# Movuino_Dongle_v0_94.net
KiCad netlist of a schematic drawn in EAGLE
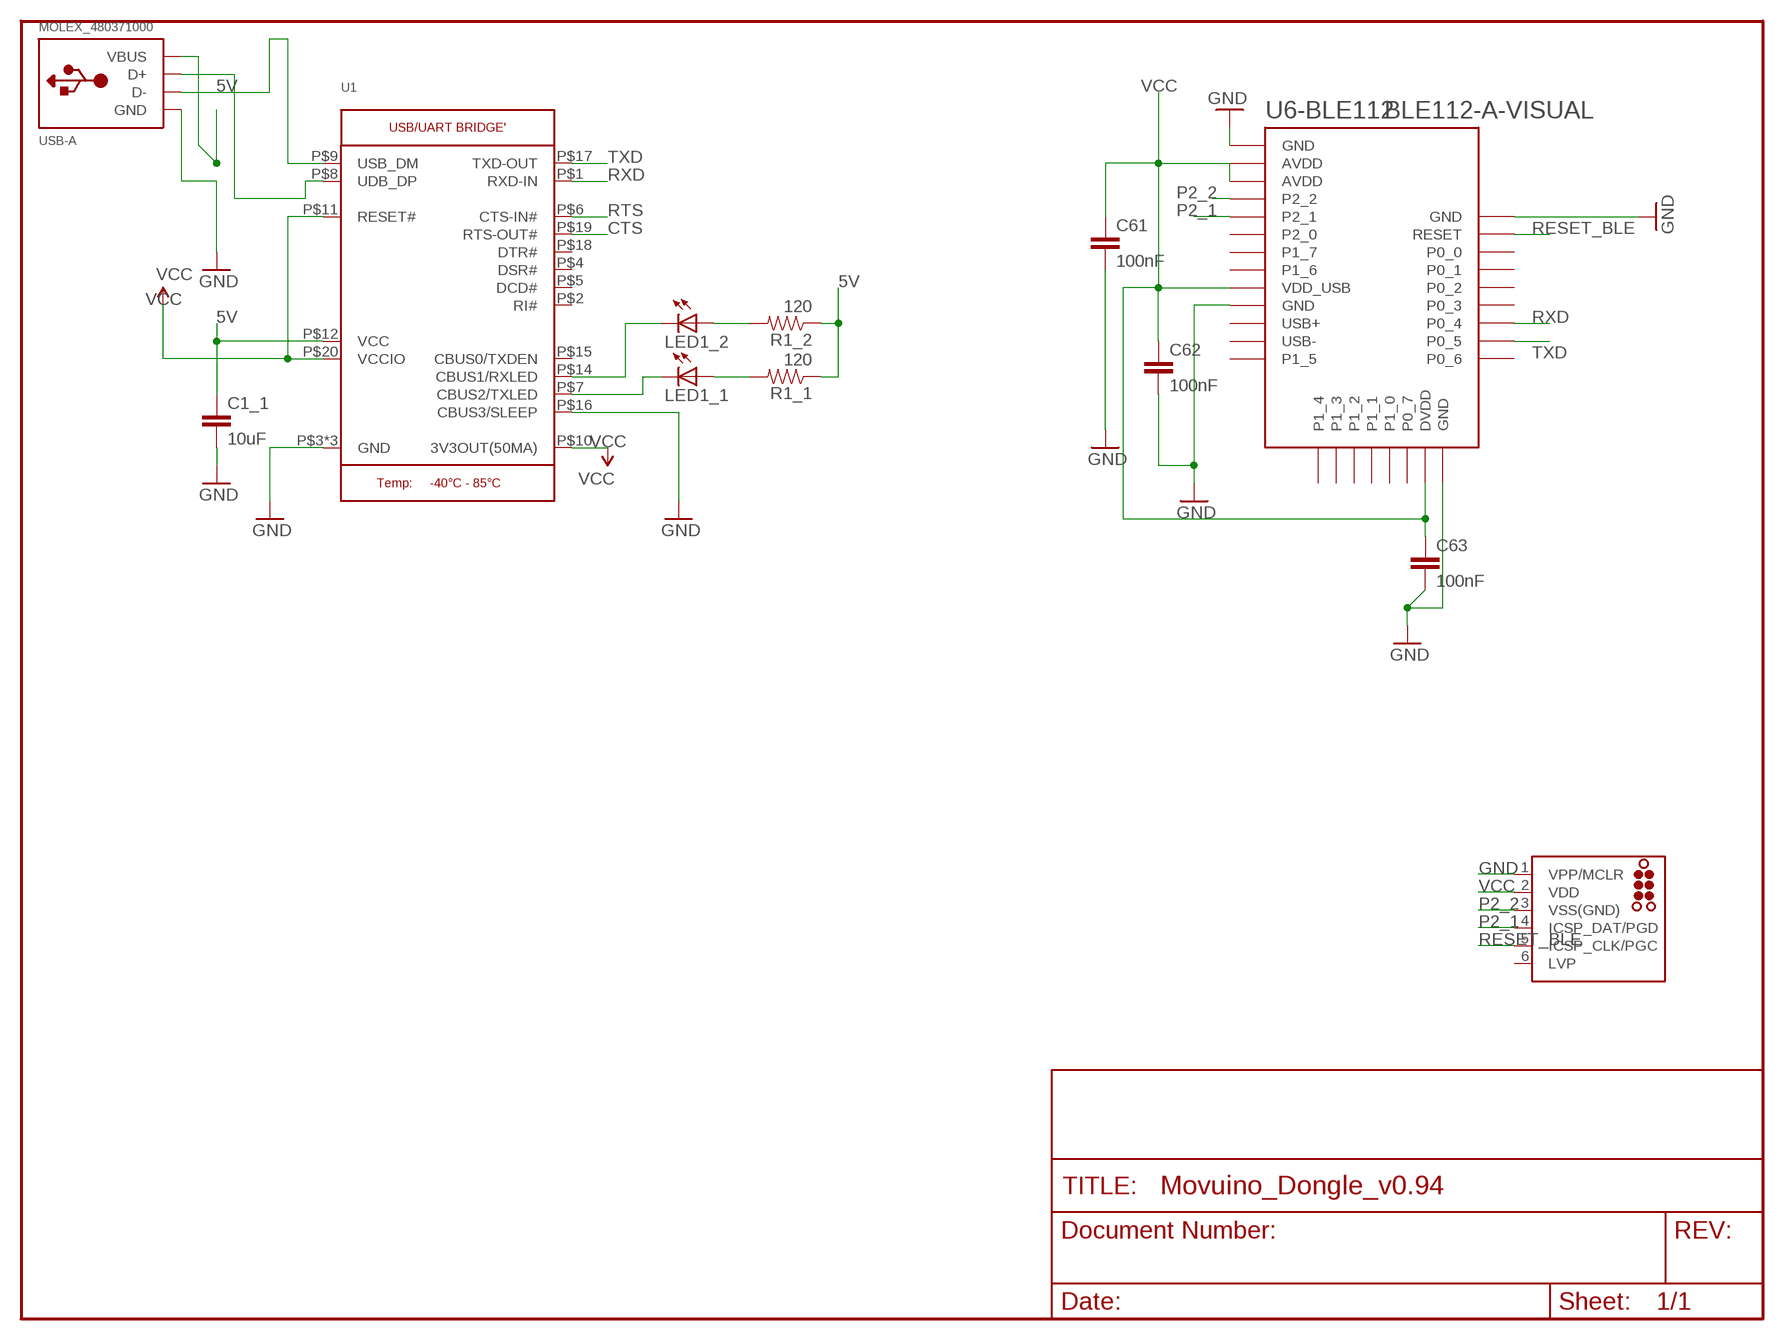
[diagram p0: schematic, sheet 1]

(export (version "E")
  (design (tool "Eeschema 10.0.6"))
  (components
    (comp (ref "C1_1")
      (value "10uF")
      (footprint "eagle-import:0402-CAP")
      (libsource (lib "eagle-import") (part "CAP0402-CAP"))
    )
    (comp (ref "C61")
      (value "100nF")
      (footprint "eagle-import:0402-CAP")
      (libsource (lib "eagle-import") (part "CAP0402-CAP"))
    )
    (comp (ref "C62")
      (value "100nF")
      (footprint "eagle-import:0402-CAP")
      (libsource (lib "eagle-import") (part "CAP0402-CAP"))
    )
    (comp (ref "C63")
      (value "100nF")
      (footprint "eagle-import:0402-CAP")
      (libsource (lib "eagle-import") (part "CAP0402-CAP"))
    )
    (comp (ref "J1")
      (value "TC2030-MCP-NL")
      (footprint "eagle-import:TC2030-MCP-NL")
      (libsource (lib "eagle-import") (part "TC2030-MCP-NL"))
    )
    (comp (ref "LED1_1")
      (value "LED0603")
      (footprint "eagle-import:LED-0603")
      (libsource (lib "eagle-import") (part "LED0603"))
    )
    (comp (ref "LED1_2")
      (value "LED0603")
      (footprint "eagle-import:LED-0603")
      (libsource (lib "eagle-import") (part "LED0603"))
    )
    (comp (ref "MOLEX_480371000")
      (value "USB-A")
      (footprint "eagle-import:MOLEX_480371000")
      (libsource (lib "eagle-import") (part "USB-A"))
    )
    (comp (ref "R1_1")
      (value "120")
      (footprint "eagle-import:0402-RES")
      (libsource (lib "eagle-import") (part "RESISTOR0402-RES"))
    )
    (comp (ref "R1_2")
      (value "120")
      (footprint "eagle-import:0402-RES")
      (libsource (lib "eagle-import") (part "RESISTOR0402-RES"))
    )
    (comp (ref "U1")
      (value "MICROBUILDER_FT231X")
      (footprint "eagle-import:MICROBUILDER_QFN20_4MM")
      (libsource (lib "eagle-import") (part "MICROBUILDER_FT231X"))
    )
    (comp (ref "U6-BLE112")
      (value "BLE112-A-VISUAL")
      (footprint "eagle-import:BLE112-A")
      (libsource (lib "eagle-import") (part "BLE112-A-VISUAL"))
    )
  )
  (nets
    (net (code "1") (name "/5V") (class "Default")
      (node (ref "C1_1") (pin "1") (pinfunction "1_1") (pintype "passive"))
      (node (ref "MOLEX_480371000") (pin "1") (pinfunction "VBUS_1") (pintype "power_in"))
      (node (ref "R1_1") (pin "1") (pinfunction "1_1") (pintype "passive"))
      (node (ref "R1_2") (pin "1") (pinfunction "1_1") (pintype "passive"))
      (node (ref "U1") (pin "P$12") (pinfunction "VCC_P$12") (pintype "power_in"))
    )
    (net (code "2") (name "/CTS") (class "Default")
      (node (ref "U1") (pin "P$19") (pinfunction "RTS-OUT#_P$19") (pintype "output"))
    )
    (net (code "3") (name "/P2_1") (class "Default")
      (node (ref "J1") (pin "4") (pinfunction "ICSP_DAT/PGD_4") (pintype "bidirectional"))
      (node (ref "U6-BLE112") (pin "P2_1") (pinfunction "P2_1_P2_1") (pintype "bidirectional"))
    )
    (net (code "4") (name "/P2_2") (class "Default")
      (node (ref "J1") (pin "3") (pinfunction "VSS(GND)_3") (pintype "power_in"))
      (node (ref "U6-BLE112") (pin "P2_2") (pinfunction "P2_2_P2_2") (pintype "bidirectional"))
    )
    (net (code "5") (name "/RESET_BLE") (class "Default")
      (node (ref "J1") (pin "5") (pinfunction "ICSP_CLK/PGC_5") (pintype "output"))
      (node (ref "U6-BLE112") (pin "RESET") (pinfunction "RESET_RESET") (pintype "input"))
    )
    (net (code "6") (name "/RTS") (class "Default")
      (node (ref "U1") (pin "P$6") (pinfunction "CTS-IN#_P$6") (pintype "input"))
    )
    (net (code "7") (name "/RXD") (class "Default")
      (node (ref "U1") (pin "P$1") (pinfunction "RXD-IN_P$1") (pintype "input"))
      (node (ref "U6-BLE112") (pin "P0_4") (pinfunction "P0_4_P0_4") (pintype "bidirectional"))
    )
    (net (code "8") (name "/TXD") (class "Default")
      (node (ref "U1") (pin "P$17") (pinfunction "TXD-OUT_P$17") (pintype "output"))
      (node (ref "U6-BLE112") (pin "P0_5") (pinfunction "P0_5_P0_5") (pintype "bidirectional"))
    )
    (net (code "9") (name "GND") (class "Default")
      (node (ref "C1_1") (pin "2") (pinfunction "2_2") (pintype "passive"))
      (node (ref "C61") (pin "2") (pinfunction "2_2") (pintype "passive"))
      (node (ref "C62") (pin "2") (pinfunction "2_2") (pintype "passive"))
      (node (ref "C63") (pin "2") (pinfunction "2_2") (pintype "passive"))
      (node (ref "J1") (pin "1") (pinfunction "VPP/MCLR_1") (pintype "passive"))
      (node (ref "MOLEX_480371000") (pin "4") (pinfunction "GND_4") (pintype "power_in"))
      (node (ref "U1") (pin "P$13") (pinfunction "GND_P$13") (pintype "power_in"))
      (node (ref "U1") (pin "P$16") (pinfunction "CBUS3/SLEEP_P$16") (pintype "bidirectional"))
      (node (ref "U1") (pin "P$21") (pinfunction "GND_P$21") (pintype "power_in"))
      (node (ref "U1") (pin "P$3") (pinfunction "GND_P$3") (pintype "power_in"))
      (node (ref "U6-BLE112") (pin "GND1") (pinfunction "GND_GND1") (pintype "power_in"))
      (node (ref "U6-BLE112") (pin "GND2") (pinfunction "GND_GND2") (pintype "power_in"))
      (node (ref "U6-BLE112") (pin "GND3") (pinfunction "GND_GND3") (pintype "power_in"))
      (node (ref "U6-BLE112") (pin "GND4") (pinfunction "GND_GND4") (pintype "power_in"))
    )
    (net (code "10") (name "Net-(LED1_1-PadA)") (class "Default")
      (node (ref "LED1_1") (pin "A") (pinfunction "A_A") (pintype "passive"))
      (node (ref "R1_1") (pin "2") (pinfunction "2_2") (pintype "passive"))
    )
    (net (code "11") (name "Net-(LED1_2-PadA)") (class "Default")
      (node (ref "LED1_2") (pin "A") (pinfunction "A_A") (pintype "passive"))
      (node (ref "R1_2") (pin "2") (pinfunction "2_2") (pintype "passive"))
    )
    (net (code "12") (name "Net-(MOLEX_480371000-D+)") (class "Default")
      (node (ref "MOLEX_480371000") (pin "3") (pinfunction "D+_3") (pintype "bidirectional"))
      (node (ref "U1") (pin "P$8") (pinfunction "UDB_DP_P$8") (pintype "input"))
    )
    (net (code "13") (name "Net-(MOLEX_480371000-D-)") (class "Default")
      (node (ref "MOLEX_480371000") (pin "2") (pinfunction "D-_2") (pintype "bidirectional"))
      (node (ref "U1") (pin "P$9") (pinfunction "USB_DM_P$9") (pintype "input"))
    )
    (net (code "14") (name "Net-(U1-CBUS1{slash}RXLED)") (class "Default")
      (node (ref "LED1_2") (pin "C") (pinfunction "C_C") (pintype "passive"))
      (node (ref "U1") (pin "P$14") (pinfunction "CBUS1/RXLED_P$14") (pintype "bidirectional"))
    )
    (net (code "15") (name "Net-(U1-CBUS2{slash}TXLED)") (class "Default")
      (node (ref "LED1_1") (pin "C") (pinfunction "C_C") (pintype "passive"))
      (node (ref "U1") (pin "P$7") (pinfunction "CBUS2/TXLED_P$7") (pintype "bidirectional"))
    )
    (net (code "16") (name "VCC") (class "Default")
      (node (ref "C61") (pin "1") (pinfunction "1_1") (pintype "passive"))
      (node (ref "C62") (pin "1") (pinfunction "1_1") (pintype "passive"))
      (node (ref "C63") (pin "1") (pinfunction "1_1") (pintype "passive"))
      (node (ref "J1") (pin "2") (pinfunction "VDD_2") (pintype "power_in"))
      (node (ref "U1") (pin "P$10") (pinfunction "3V3OUT(50MA)_P$10") (pintype "power_in"))
      (node (ref "U1") (pin "P$11") (pinfunction "RESET#_P$11") (pintype "input"))
      (node (ref "U1") (pin "P$20") (pinfunction "VCCIO_P$20") (pintype "power_in"))
      (node (ref "U6-BLE112") (pin "AVDD1") (pinfunction "AVDD_AVDD1") (pintype "power_in"))
      (node (ref "U6-BLE112") (pin "AVDD2") (pinfunction "AVDD_AVDD2") (pintype "power_in"))
      (node (ref "U6-BLE112") (pin "DVDD") (pinfunction "DVDD_DVDD") (pintype "power_in"))
      (node (ref "U6-BLE112") (pin "VDD_USB") (pinfunction "VDD_USB_VDD_USB") (pintype "power_in"))
    )
    (net (code "17") (name "unconnected-(J1-LVP-Pad6)") (class "Default")
      (node (ref "J1") (pin "6") (pinfunction "LVP_6") (pintype "bidirectional"))
    )
    (net (code "18") (name "unconnected-(U1-CBUS0{slash}TXDEN-PadP$15)") (class "Default")
      (node (ref "U1") (pin "P$15") (pinfunction "CBUS0/TXDEN_P$15") (pintype "bidirectional"))
    )
    (net (code "19") (name "unconnected-(U1-DCD#-PadP$5)") (class "Default")
      (node (ref "U1") (pin "P$5") (pinfunction "DCD#_P$5") (pintype "input"))
    )
    (net (code "20") (name "unconnected-(U1-DSR#-PadP$4)") (class "Default")
      (node (ref "U1") (pin "P$4") (pinfunction "DSR#_P$4") (pintype "input"))
    )
    (net (code "21") (name "unconnected-(U1-DTR#-PadP$18)") (class "Default")
      (node (ref "U1") (pin "P$18") (pinfunction "DTR#_P$18") (pintype "output"))
    )
    (net (code "22") (name "unconnected-(U1-RI#-PadP$2)") (class "Default")
      (node (ref "U1") (pin "P$2") (pinfunction "RI#_P$2") (pintype "input"))
    )
    (net (code "23") (name "unconnected-(U6-BLE112-PadP0_0)") (class "Default")
      (node (ref "U6-BLE112") (pin "P0_0") (pinfunction "P0_0_P0_0") (pintype "bidirectional"))
    )
    (net (code "24") (name "unconnected-(U6-BLE112-PadP0_1)") (class "Default")
      (node (ref "U6-BLE112") (pin "P0_1") (pinfunction "P0_1_P0_1") (pintype "bidirectional"))
    )
    (net (code "25") (name "unconnected-(U6-BLE112-PadP0_2)") (class "Default")
      (node (ref "U6-BLE112") (pin "P0_2") (pinfunction "P0_2_P0_2") (pintype "bidirectional"))
    )
    (net (code "26") (name "unconnected-(U6-BLE112-PadP0_3)") (class "Default")
      (node (ref "U6-BLE112") (pin "P0_3") (pinfunction "P0_3_P0_3") (pintype "bidirectional"))
    )
    (net (code "27") (name "unconnected-(U6-BLE112-PadP0_6)") (class "Default")
      (node (ref "U6-BLE112") (pin "P0_6") (pinfunction "P0_6_P0_6") (pintype "bidirectional"))
    )
    (net (code "28") (name "unconnected-(U6-BLE112-PadP0_7)") (class "Default")
      (node (ref "U6-BLE112") (pin "P0_7") (pinfunction "P0_7_P0_7") (pintype "bidirectional"))
    )
    (net (code "29") (name "unconnected-(U6-BLE112-PadP1_0)") (class "Default")
      (node (ref "U6-BLE112") (pin "P1_0") (pinfunction "P1_0_P1_0") (pintype "bidirectional"))
    )
    (net (code "30") (name "unconnected-(U6-BLE112-PadP1_1)") (class "Default")
      (node (ref "U6-BLE112") (pin "P1_1") (pinfunction "P1_1_P1_1") (pintype "bidirectional"))
    )
    (net (code "31") (name "unconnected-(U6-BLE112-PadP1_2)") (class "Default")
      (node (ref "U6-BLE112") (pin "P1_2") (pinfunction "P1_2_P1_2") (pintype "bidirectional"))
    )
    (net (code "32") (name "unconnected-(U6-BLE112-PadP1_3)") (class "Default")
      (node (ref "U6-BLE112") (pin "P1_3") (pinfunction "P1_3_P1_3") (pintype "bidirectional"))
    )
    (net (code "33") (name "unconnected-(U6-BLE112-PadP1_4)") (class "Default")
      (node (ref "U6-BLE112") (pin "P1_4") (pinfunction "P1_4_P1_4") (pintype "bidirectional"))
    )
    (net (code "34") (name "unconnected-(U6-BLE112-PadP1_5)") (class "Default")
      (node (ref "U6-BLE112") (pin "P1_5") (pinfunction "P1_5_P1_5") (pintype "bidirectional"))
    )
    (net (code "35") (name "unconnected-(U6-BLE112-PadP1_6)") (class "Default")
      (node (ref "U6-BLE112") (pin "P1_6") (pinfunction "P1_6_P1_6") (pintype "bidirectional"))
    )
    (net (code "36") (name "unconnected-(U6-BLE112-PadP1_7)") (class "Default")
      (node (ref "U6-BLE112") (pin "P1_7") (pinfunction "P1_7_P1_7") (pintype "bidirectional"))
    )
    (net (code "37") (name "unconnected-(U6-BLE112-PadP2_0)") (class "Default")
      (node (ref "U6-BLE112") (pin "P2_0") (pinfunction "P2_0_P2_0") (pintype "bidirectional"))
    )
    (net (code "38") (name "unconnected-(U6-BLE112-PadUSB+)") (class "Default")
      (node (ref "U6-BLE112") (pin "USB+") (pinfunction "USB+_USB+") (pintype "bidirectional"))
    )
    (net (code "39") (name "unconnected-(U6-BLE112-PadUSB-)") (class "Default")
      (node (ref "U6-BLE112") (pin "USB-") (pinfunction "USB-_USB-") (pintype "bidirectional"))
    )
  )
)
